# ADC_REF.net
KiCad netlist of a schematic drawn in Altium Designer
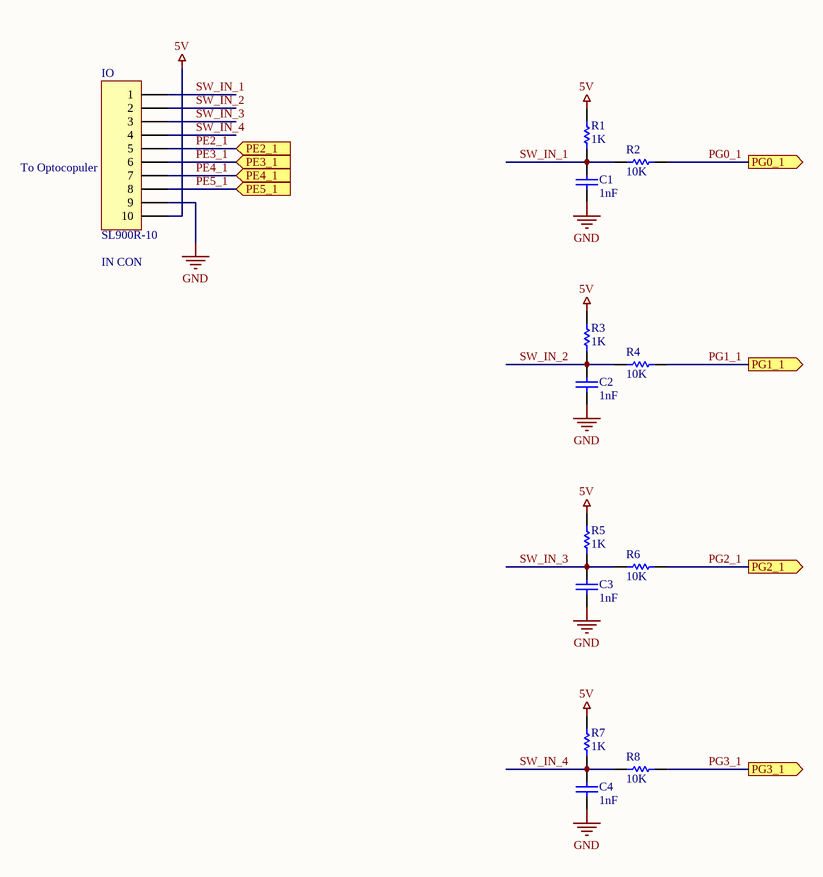
[diagram p0: ADC_REF.SchDoc]

(export (version "E")
  (design (tool "Eeschema 10.0.6"))
  (components
    (comp (ref "C1")
      (value "1nF")
      (footprint "CAPC2013X140X50NL20T25")
      (fields
        (field (name "MANUFACTURER") "AVX Interconnect / Elco")
        (field (name "PART NUMBER") "08051A102JAT2A")
      )
      (libsource (lib "Altium Content Vault") (part "CAP"))
    )
    (comp (ref "C2")
      (value "1nF")
      (footprint "CAPC2013X140X50NL20T25")
      (fields
        (field (name "MANUFACTURER") "AVX Interconnect / Elco")
        (field (name "PART NUMBER") "08051A102JAT2A")
      )
      (libsource (lib "Altium Content Vault") (part "CAP"))
    )
    (comp (ref "C3")
      (value "1nF")
      (footprint "CAPC2013X140X50NL20T25")
      (fields
        (field (name "MANUFACTURER") "AVX Interconnect / Elco")
        (field (name "PART NUMBER") "08051A102JAT2A")
      )
      (libsource (lib "Altium Content Vault") (part "CAP"))
    )
    (comp (ref "C4")
      (value "1nF")
      (footprint "CAPC2013X140X50NL20T25")
      (fields
        (field (name "MANUFACTURER") "AVX Interconnect / Elco")
        (field (name "PART NUMBER") "08051A102JAT2A")
      )
      (libsource (lib "Altium Content Vault") (part "CAP"))
    )
    (comp (ref "IO")
      (value "SL900R-10")
      (footprint "SR-900R-10")
      (description "Header, 10-Pin")
      (fields (field (name "PUBLISHER") "Altium Limited"))
      (libsource (lib "Miscellaneous Connectors") (part "Header 10"))
    )
    (comp (ref "R1")
      (value "1K")
      (footprint "RESC2113X50X35ML15T15")
      (description "Chip Resistor, 4.7 KOhm, +/- 1%, 0.125 W, -55 to 155 degC, 0805 (2012 Metric), RoHS, Tape and Reel")
      (fields (field (name "TOLERANCE") "1%") (field (name "MANUFACTURER") "Vishay Semiconductor"))
      (libsource (lib "Altium Content Vault") (part "RES-2"))
    )
    (comp (ref "R2")
      (value "10K")
      (footprint "RESC2113X50X35ML15T15")
      (description "Chip Resistor, 4.7 KOhm, +/- 1%, 0.125 W, -55 to 155 degC, 0805 (2012 Metric), RoHS, Tape and Reel")
      (fields (field (name "TOLERANCE") "1%") (field (name "MANUFACTURER") "Vishay Semiconductor"))
      (libsource (lib "Altium Content Vault") (part "RES-2"))
    )
    (comp (ref "R3")
      (value "1K")
      (footprint "RESC2113X50X35ML15T15")
      (description "Chip Resistor, 4.7 KOhm, +/- 1%, 0.125 W, -55 to 155 degC, 0805 (2012 Metric), RoHS, Tape and Reel")
      (fields (field (name "TOLERANCE") "1%") (field (name "MANUFACTURER") "Vishay Semiconductor"))
      (libsource (lib "Altium Content Vault") (part "RES-2"))
    )
    (comp (ref "R4")
      (value "10K")
      (footprint "RESC2113X50X35ML15T15")
      (description "Chip Resistor, 4.7 KOhm, +/- 1%, 0.125 W, -55 to 155 degC, 0805 (2012 Metric), RoHS, Tape and Reel")
      (fields (field (name "TOLERANCE") "1%") (field (name "MANUFACTURER") "Vishay Semiconductor"))
      (libsource (lib "Altium Content Vault") (part "RES-2"))
    )
    (comp (ref "R5")
      (value "1K")
      (footprint "RESC2113X50X35ML15T15")
      (description "Chip Resistor, 4.7 KOhm, +/- 1%, 0.125 W, -55 to 155 degC, 0805 (2012 Metric), RoHS, Tape and Reel")
      (fields (field (name "TOLERANCE") "1%") (field (name "MANUFACTURER") "Vishay Semiconductor"))
      (libsource (lib "Altium Content Vault") (part "RES-2"))
    )
    (comp (ref "R6")
      (value "10K")
      (footprint "RESC2113X50X35ML15T15")
      (description "Chip Resistor, 4.7 KOhm, +/- 1%, 0.125 W, -55 to 155 degC, 0805 (2012 Metric), RoHS, Tape and Reel")
      (fields (field (name "TOLERANCE") "1%") (field (name "MANUFACTURER") "Vishay Semiconductor"))
      (libsource (lib "Altium Content Vault") (part "RES-2"))
    )
    (comp (ref "R7")
      (value "1K")
      (footprint "RESC2113X50X35ML15T15")
      (description "Chip Resistor, 4.7 KOhm, +/- 1%, 0.125 W, -55 to 155 degC, 0805 (2012 Metric), RoHS, Tape and Reel")
      (fields (field (name "TOLERANCE") "1%") (field (name "MANUFACTURER") "Vishay Semiconductor"))
      (libsource (lib "Altium Content Vault") (part "RES-2"))
    )
    (comp (ref "R8")
      (value "10K")
      (footprint "RESC2113X50X35ML15T15")
      (description "Chip Resistor, 4.7 KOhm, +/- 1%, 0.125 W, -55 to 155 degC, 0805 (2012 Metric), RoHS, Tape and Reel")
      (fields (field (name "TOLERANCE") "1%") (field (name "MANUFACTURER") "Vishay Semiconductor"))
      (libsource (lib "Altium Content Vault") (part "RES-2"))
    )
  )
  (nets
    (net (code "1") (name "/PE2_1") (class "Default")
      (node (ref "IO") (pin "5") (pinfunction "5_5") (pintype "passive"))
    )
    (net (code "2") (name "/PE3_1") (class "Default")
      (node (ref "IO") (pin "6") (pinfunction "6_6") (pintype "passive"))
    )
    (net (code "3") (name "/PE4_1") (class "Default")
      (node (ref "IO") (pin "7") (pinfunction "7_7") (pintype "passive"))
    )
    (net (code "4") (name "/PE5_1") (class "Default")
      (node (ref "IO") (pin "8") (pinfunction "8_8") (pintype "passive"))
    )
    (net (code "5") (name "/PG0_1") (class "Default")
      (node (ref "R2") (pin "1") (pinfunction "1_1") (pintype "passive"))
    )
    (net (code "6") (name "/PG1_1") (class "Default")
      (node (ref "R4") (pin "1") (pinfunction "1_1") (pintype "passive"))
    )
    (net (code "7") (name "/PG2_1") (class "Default")
      (node (ref "R6") (pin "1") (pinfunction "1_1") (pintype "passive"))
    )
    (net (code "8") (name "/PG3_1") (class "Default")
      (node (ref "R8") (pin "1") (pinfunction "1_1") (pintype "passive"))
    )
    (net (code "9") (name "/SW_IN_1") (class "Default")
      (node (ref "C1") (pin "2") (pinfunction "2_2") (pintype "passive"))
      (node (ref "IO") (pin "1") (pinfunction "1_1") (pintype "passive"))
      (node (ref "R1") (pin "1") (pinfunction "1_1") (pintype "passive"))
      (node (ref "R2") (pin "2") (pinfunction "2_2") (pintype "passive"))
    )
    (net (code "10") (name "/SW_IN_2") (class "Default")
      (node (ref "C2") (pin "2") (pinfunction "2_2") (pintype "passive"))
      (node (ref "IO") (pin "2") (pinfunction "2_2") (pintype "passive"))
      (node (ref "R3") (pin "1") (pinfunction "1_1") (pintype "passive"))
      (node (ref "R4") (pin "2") (pinfunction "2_2") (pintype "passive"))
    )
    (net (code "11") (name "/SW_IN_3") (class "Default")
      (node (ref "C3") (pin "2") (pinfunction "2_2") (pintype "passive"))
      (node (ref "IO") (pin "3") (pinfunction "3_3") (pintype "passive"))
      (node (ref "R5") (pin "1") (pinfunction "1_1") (pintype "passive"))
      (node (ref "R6") (pin "2") (pinfunction "2_2") (pintype "passive"))
    )
    (net (code "12") (name "/SW_IN_4") (class "Default")
      (node (ref "C4") (pin "2") (pinfunction "2_2") (pintype "passive"))
      (node (ref "IO") (pin "4") (pinfunction "4_4") (pintype "passive"))
      (node (ref "R7") (pin "1") (pinfunction "1_1") (pintype "passive"))
      (node (ref "R8") (pin "2") (pinfunction "2_2") (pintype "passive"))
    )
    (net (code "13") (name "5V") (class "Default")
      (node (ref "IO") (pin "10") (pinfunction "10_10") (pintype "passive"))
      (node (ref "R1") (pin "2") (pinfunction "2_2") (pintype "passive"))
      (node (ref "R3") (pin "2") (pinfunction "2_2") (pintype "passive"))
      (node (ref "R5") (pin "2") (pinfunction "2_2") (pintype "passive"))
      (node (ref "R7") (pin "2") (pinfunction "2_2") (pintype "passive"))
    )
    (net (code "14") (name "GND") (class "Default")
      (node (ref "C1") (pin "1") (pinfunction "1_1") (pintype "passive"))
      (node (ref "C2") (pin "1") (pinfunction "1_1") (pintype "passive"))
      (node (ref "C3") (pin "1") (pinfunction "1_1") (pintype "passive"))
      (node (ref "C4") (pin "1") (pinfunction "1_1") (pintype "passive"))
      (node (ref "IO") (pin "9") (pinfunction "9_9") (pintype "passive"))
    )
  )
)
